# schematics.net
KiCad netlist of a schematic drawn in EasyEDA
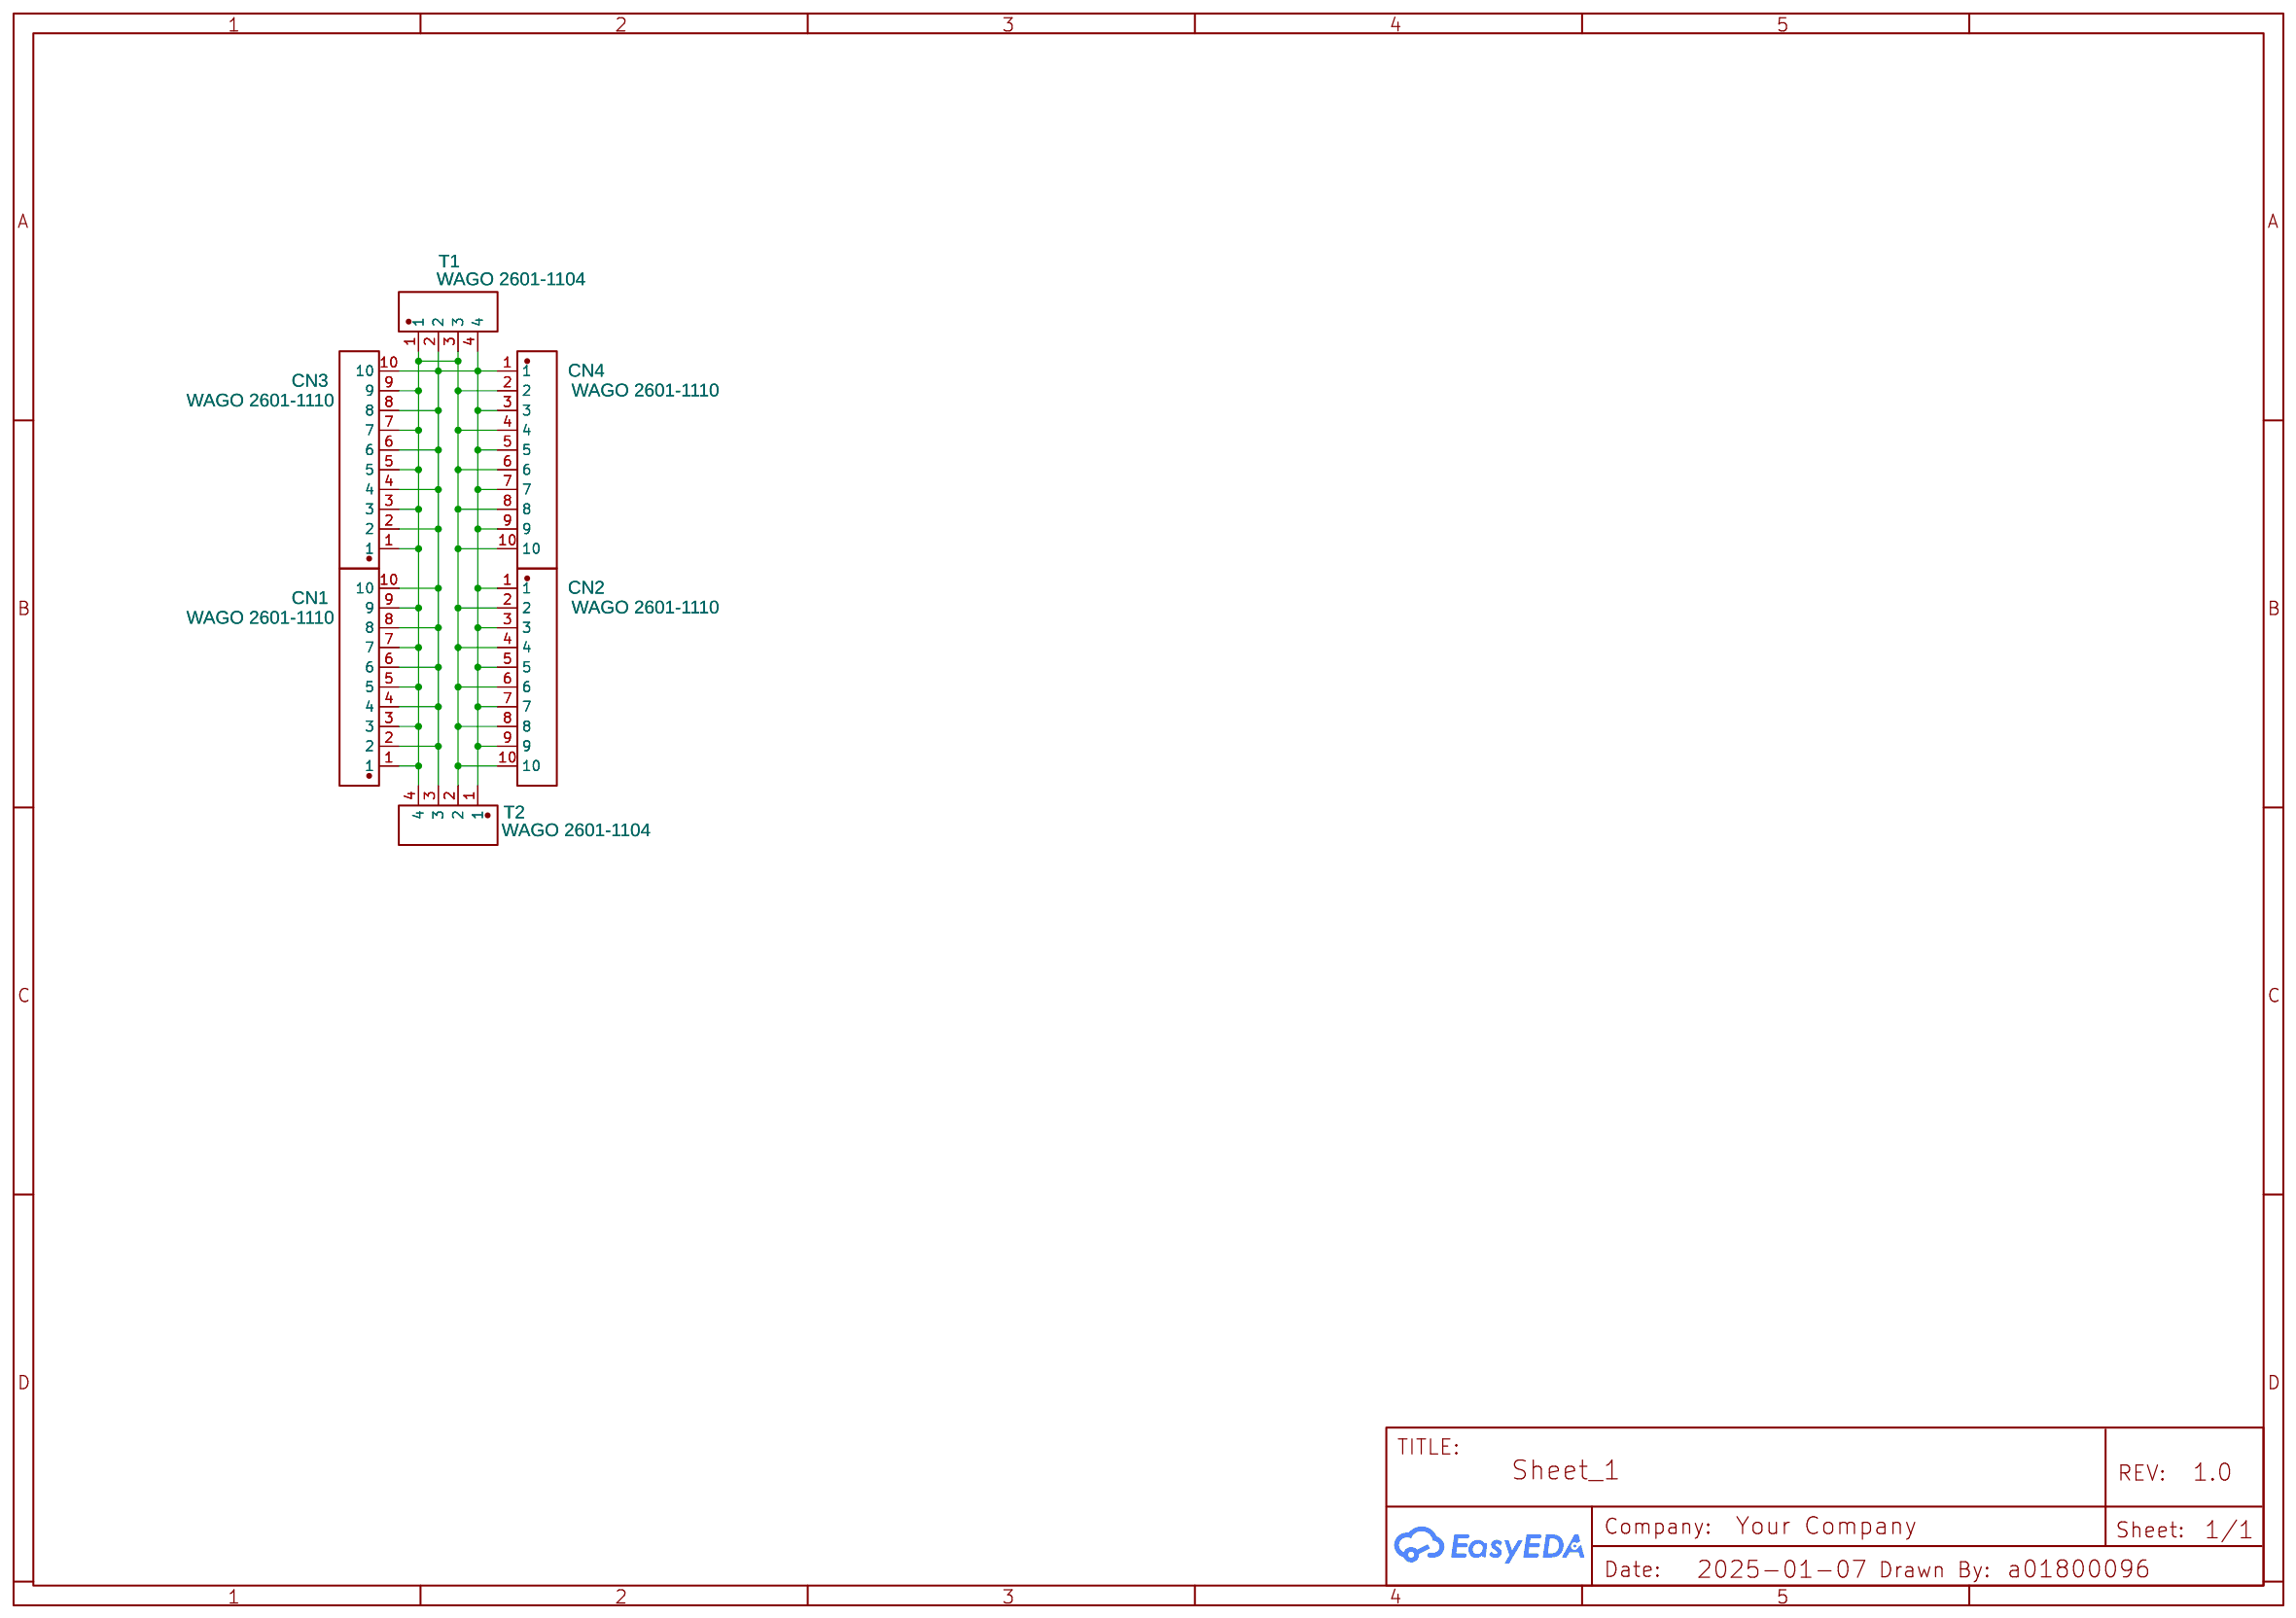
[diagram p0: PCB en Paralelo]
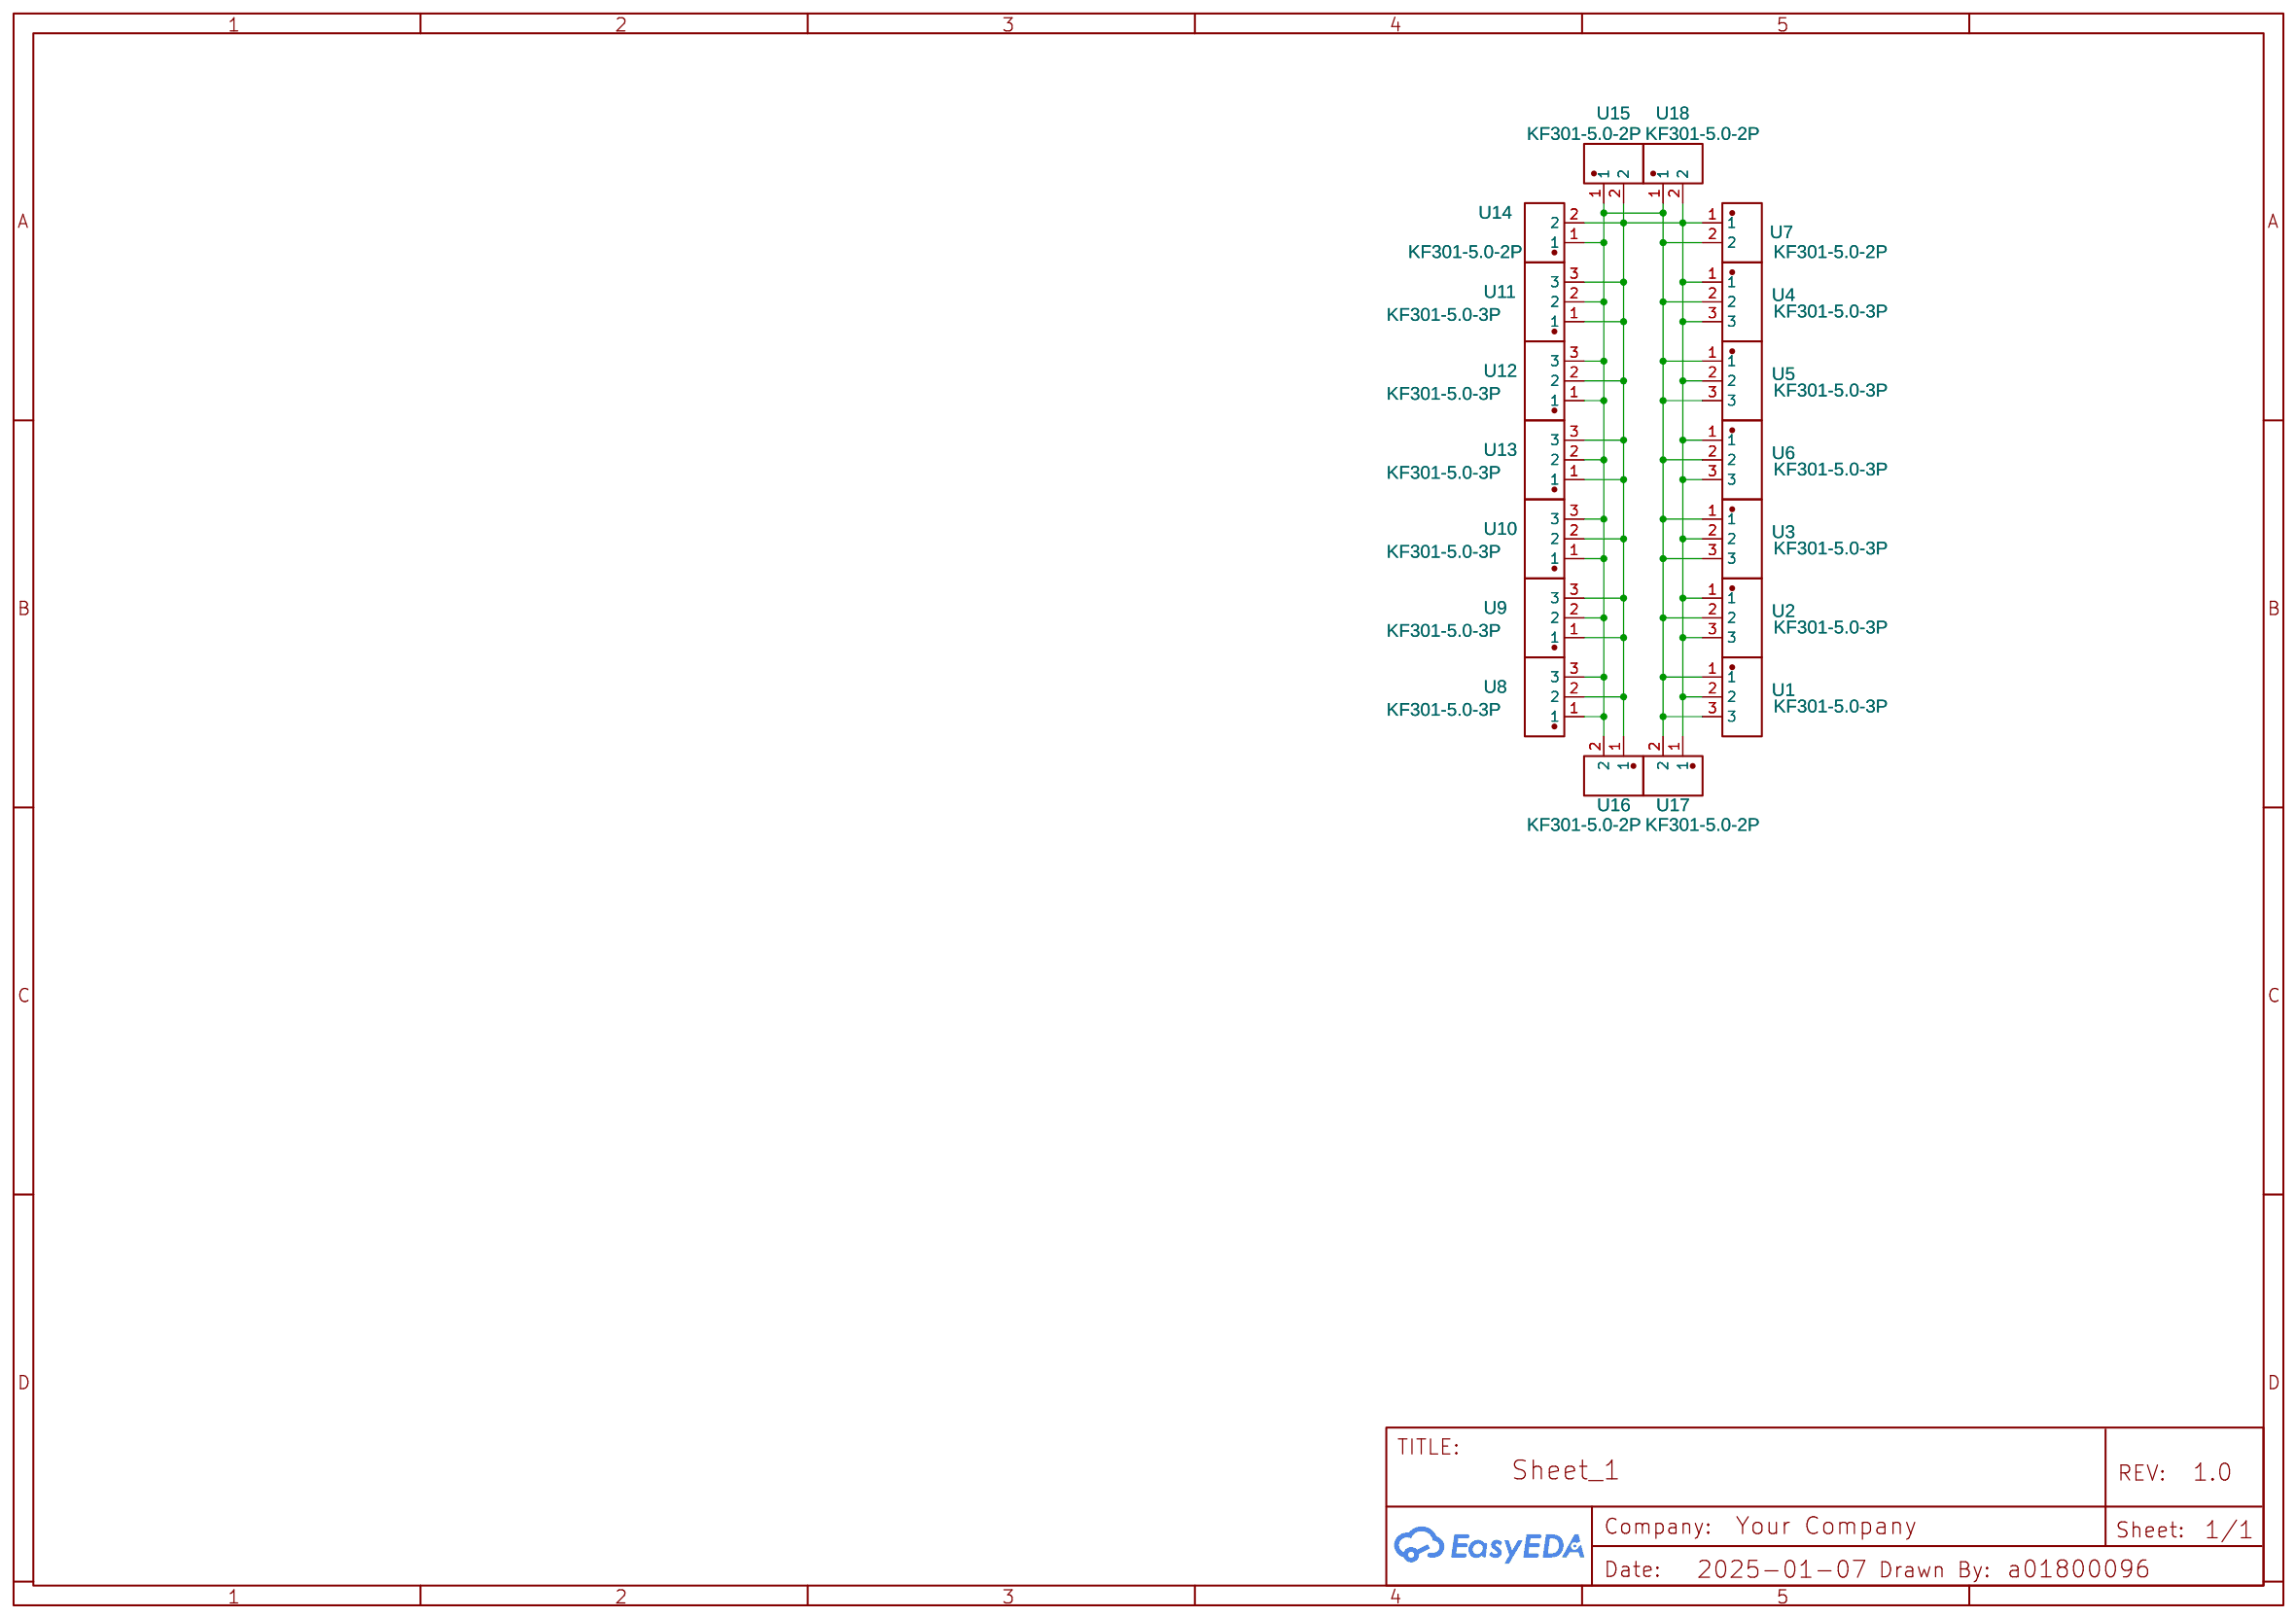
[diagram p1: PCB Final]

(export (version "E")
  (design (tool "Eeschema 10.0.6"))
  (components
    (comp (ref "CN1")
      (value "WAGO 2601-1110")
      (fields (field (name "Manufacturer Part") "CONNECTOR"))
      (libsource (lib "") (part "WAGO 2601-1110_1"))
    )
    (comp (ref "CN2")
      (value "WAGO 2601-1110")
      (fields (field (name "Manufacturer Part") "CONNECTOR"))
      (libsource (lib "") (part "WAGO 2601-1110"))
    )
    (comp (ref "CN3")
      (value "WAGO 2601-1110")
      (fields (field (name "Manufacturer Part") "CONNECTOR"))
      (libsource (lib "") (part "WAGO 2601-1110_1"))
    )
    (comp (ref "CN4")
      (value "WAGO 2601-1110")
      (fields (field (name "Manufacturer Part") "CONNECTOR"))
      (libsource (lib "") (part "WAGO 2601-1110"))
    )
    (comp (ref "T1") (value "WAGO 2601-1104") (libsource (lib "") (part "WAGO 2601-1104")))
    (comp (ref "T2") (value "WAGO 2601-1104") (libsource (lib "") (part "WAGO 2601-1104_1")))
    (comp (ref "U1")
      (value "KF301-5.0-3P")
      (fields (field (name "Manufacturer") "KEFA(科发)"))
      (libsource (lib "") (part "KF301-5.0-3P_1"))
    )
    (comp (ref "U2")
      (value "KF301-5.0-3P")
      (fields (field (name "Manufacturer") "KEFA(科发)"))
      (libsource (lib "") (part "KF301-5.0-3P_1"))
    )
    (comp (ref "U3")
      (value "KF301-5.0-3P")
      (fields (field (name "Manufacturer") "KEFA(科发)"))
      (libsource (lib "") (part "KF301-5.0-3P_1"))
    )
    (comp (ref "U4")
      (value "KF301-5.0-3P")
      (fields (field (name "Manufacturer") "KEFA(科发)"))
      (libsource (lib "") (part "KF301-5.0-3P_1"))
    )
    (comp (ref "U5")
      (value "KF301-5.0-3P")
      (fields (field (name "Manufacturer") "KEFA(科发)"))
      (libsource (lib "") (part "KF301-5.0-3P_1"))
    )
    (comp (ref "U6")
      (value "KF301-5.0-3P")
      (fields (field (name "Manufacturer") "KEFA(科发)"))
      (libsource (lib "") (part "KF301-5.0-3P_1"))
    )
    (comp (ref "U7")
      (value "KF301-5.0-2P")
      (fields (field (name "Manufacturer") "KEFA(科发)"))
      (libsource (lib "") (part "KF301-5.0-2P"))
    )
    (comp (ref "U8")
      (value "KF301-5.0-3P")
      (fields (field (name "Manufacturer") "KEFA(科发)"))
      (libsource (lib "") (part "KF301-5.0-3P"))
    )
    (comp (ref "U9")
      (value "KF301-5.0-3P")
      (fields (field (name "Manufacturer") "KEFA(科发)"))
      (libsource (lib "") (part "KF301-5.0-3P"))
    )
    (comp (ref "U10")
      (value "KF301-5.0-3P")
      (fields (field (name "Manufacturer") "KEFA(科发)"))
      (libsource (lib "") (part "KF301-5.0-3P"))
    )
    (comp (ref "U11")
      (value "KF301-5.0-3P")
      (fields (field (name "Manufacturer") "KEFA(科发)"))
      (libsource (lib "") (part "KF301-5.0-3P"))
    )
    (comp (ref "U12")
      (value "KF301-5.0-3P")
      (fields (field (name "Manufacturer") "KEFA(科发)"))
      (libsource (lib "") (part "KF301-5.0-3P"))
    )
    (comp (ref "U13")
      (value "KF301-5.0-3P")
      (fields (field (name "Manufacturer") "KEFA(科发)"))
      (libsource (lib "") (part "KF301-5.0-3P"))
    )
    (comp (ref "U14")
      (value "KF301-5.0-2P")
      (fields (field (name "Manufacturer") "KEFA(科发)"))
      (libsource (lib "") (part "KF301-5.0-2P_3"))
    )
    (comp (ref "U15")
      (value "KF301-5.0-2P")
      (fields (field (name "Manufacturer") "KEFA(科发)"))
      (libsource (lib "") (part "KF301-5.0-2P_2"))
    )
    (comp (ref "U16")
      (value "KF301-5.0-2P")
      (fields (field (name "Manufacturer") "KEFA(科发)"))
      (libsource (lib "") (part "KF301-5.0-2P_1"))
    )
    (comp (ref "U17")
      (value "KF301-5.0-2P")
      (fields (field (name "Manufacturer") "KEFA(科发)"))
      (libsource (lib "") (part "KF301-5.0-2P_1"))
    )
    (comp (ref "U18")
      (value "KF301-5.0-2P")
      (fields (field (name "Manufacturer") "KEFA(科发)"))
      (libsource (lib "") (part "KF301-5.0-2P_2"))
    )
  )
  (nets
    (net (code "1") (name "Net-(CN1-Pad1)") (class "Default")
      (node (ref "CN1") (pin "1") (pinfunction "1_1") (pintype "unspecified"))
      (node (ref "CN1") (pin "3") (pinfunction "3_3") (pintype "unspecified"))
      (node (ref "CN1") (pin "5") (pinfunction "5_5") (pintype "unspecified"))
      (node (ref "CN1") (pin "7") (pinfunction "7_7") (pintype "unspecified"))
      (node (ref "CN1") (pin "9") (pinfunction "9_9") (pintype "unspecified"))
      (node (ref "CN2") (pin "10") (pinfunction "10_10") (pintype "unspecified"))
      (node (ref "CN2") (pin "2") (pinfunction "2_2") (pintype "unspecified"))
      (node (ref "CN2") (pin "4") (pinfunction "4_4") (pintype "unspecified"))
      (node (ref "CN2") (pin "6") (pinfunction "6_6") (pintype "unspecified"))
      (node (ref "CN2") (pin "8") (pinfunction "8_8") (pintype "unspecified"))
      (node (ref "CN3") (pin "1") (pinfunction "1_1") (pintype "unspecified"))
      (node (ref "CN3") (pin "3") (pinfunction "3_3") (pintype "unspecified"))
      (node (ref "CN3") (pin "5") (pinfunction "5_5") (pintype "unspecified"))
      (node (ref "CN3") (pin "7") (pinfunction "7_7") (pintype "unspecified"))
      (node (ref "CN3") (pin "9") (pinfunction "9_9") (pintype "unspecified"))
      (node (ref "CN4") (pin "10") (pinfunction "10_10") (pintype "unspecified"))
      (node (ref "CN4") (pin "2") (pinfunction "2_2") (pintype "unspecified"))
      (node (ref "CN4") (pin "4") (pinfunction "4_4") (pintype "unspecified"))
      (node (ref "CN4") (pin "6") (pinfunction "6_6") (pintype "unspecified"))
      (node (ref "CN4") (pin "8") (pinfunction "8_8") (pintype "unspecified"))
      (node (ref "T1") (pin "1") (pinfunction "1_1") (pintype "unspecified"))
      (node (ref "T1") (pin "3") (pinfunction "3_3") (pintype "unspecified"))
      (node (ref "T2") (pin "2") (pinfunction "2_2") (pintype "unspecified"))
      (node (ref "T2") (pin "4") (pinfunction "4_4") (pintype "unspecified"))
    )
    (net (code "2") (name "Net-(CN1-Pad10)") (class "Default")
      (node (ref "CN1") (pin "10") (pinfunction "10_10") (pintype "unspecified"))
      (node (ref "CN1") (pin "2") (pinfunction "2_2") (pintype "unspecified"))
      (node (ref "CN1") (pin "4") (pinfunction "4_4") (pintype "unspecified"))
      (node (ref "CN1") (pin "6") (pinfunction "6_6") (pintype "unspecified"))
      (node (ref "CN1") (pin "8") (pinfunction "8_8") (pintype "unspecified"))
      (node (ref "CN2") (pin "1") (pinfunction "1_1") (pintype "unspecified"))
      (node (ref "CN2") (pin "3") (pinfunction "3_3") (pintype "unspecified"))
      (node (ref "CN2") (pin "5") (pinfunction "5_5") (pintype "unspecified"))
      (node (ref "CN2") (pin "7") (pinfunction "7_7") (pintype "unspecified"))
      (node (ref "CN2") (pin "9") (pinfunction "9_9") (pintype "unspecified"))
      (node (ref "CN3") (pin "10") (pinfunction "10_10") (pintype "unspecified"))
      (node (ref "CN3") (pin "2") (pinfunction "2_2") (pintype "unspecified"))
      (node (ref "CN3") (pin "4") (pinfunction "4_4") (pintype "unspecified"))
      (node (ref "CN3") (pin "6") (pinfunction "6_6") (pintype "unspecified"))
      (node (ref "CN3") (pin "8") (pinfunction "8_8") (pintype "unspecified"))
      (node (ref "CN4") (pin "1") (pinfunction "1_1") (pintype "unspecified"))
      (node (ref "CN4") (pin "3") (pinfunction "3_3") (pintype "unspecified"))
      (node (ref "CN4") (pin "5") (pinfunction "5_5") (pintype "unspecified"))
      (node (ref "CN4") (pin "7") (pinfunction "7_7") (pintype "unspecified"))
      (node (ref "CN4") (pin "9") (pinfunction "9_9") (pintype "unspecified"))
      (node (ref "T1") (pin "2") (pinfunction "2_2") (pintype "unspecified"))
      (node (ref "T1") (pin "4") (pinfunction "4_4") (pintype "unspecified"))
      (node (ref "T2") (pin "1") (pinfunction "1_1") (pintype "unspecified"))
      (node (ref "T2") (pin "3") (pinfunction "3_3") (pintype "unspecified"))
    )
    (net (code "3") (name "Net-(U1-Pad1)") (class "Default")
      (node (ref "U1") (pin "1") (pinfunction "1_1") (pintype "unspecified"))
      (node (ref "U1") (pin "3") (pinfunction "3_3") (pintype "unspecified"))
      (node (ref "U10") (pin "1") (pinfunction "1_1") (pintype "unspecified"))
      (node (ref "U10") (pin "3") (pinfunction "3_3") (pintype "unspecified"))
      (node (ref "U11") (pin "2") (pinfunction "2_2") (pintype "unspecified"))
      (node (ref "U12") (pin "1") (pinfunction "1_1") (pintype "unspecified"))
      (node (ref "U12") (pin "3") (pinfunction "3_3") (pintype "unspecified"))
      (node (ref "U13") (pin "2") (pinfunction "2_2") (pintype "unspecified"))
      (node (ref "U14") (pin "1") (pinfunction "1_1") (pintype "unspecified"))
      (node (ref "U15") (pin "1") (pinfunction "1_1") (pintype "unspecified"))
      (node (ref "U16") (pin "2") (pinfunction "2_2") (pintype "unspecified"))
      (node (ref "U17") (pin "2") (pinfunction "2_2") (pintype "unspecified"))
      (node (ref "U18") (pin "1") (pinfunction "1_1") (pintype "unspecified"))
      (node (ref "U2") (pin "2") (pinfunction "2_2") (pintype "unspecified"))
      (node (ref "U3") (pin "1") (pinfunction "1_1") (pintype "unspecified"))
      (node (ref "U3") (pin "3") (pinfunction "3_3") (pintype "unspecified"))
      (node (ref "U4") (pin "2") (pinfunction "2_2") (pintype "unspecified"))
      (node (ref "U5") (pin "1") (pinfunction "1_1") (pintype "unspecified"))
      (node (ref "U5") (pin "3") (pinfunction "3_3") (pintype "unspecified"))
      (node (ref "U6") (pin "2") (pinfunction "2_2") (pintype "unspecified"))
      (node (ref "U7") (pin "2") (pinfunction "2_2") (pintype "unspecified"))
      (node (ref "U8") (pin "1") (pinfunction "1_1") (pintype "unspecified"))
      (node (ref "U8") (pin "3") (pinfunction "3_3") (pintype "unspecified"))
      (node (ref "U9") (pin "2") (pinfunction "2_2") (pintype "unspecified"))
    )
    (net (code "4") (name "Net-(U1-Pad2)") (class "Default")
      (node (ref "U1") (pin "2") (pinfunction "2_2") (pintype "unspecified"))
      (node (ref "U10") (pin "2") (pinfunction "2_2") (pintype "unspecified"))
      (node (ref "U11") (pin "1") (pinfunction "1_1") (pintype "unspecified"))
      (node (ref "U11") (pin "3") (pinfunction "3_3") (pintype "unspecified"))
      (node (ref "U12") (pin "2") (pinfunction "2_2") (pintype "unspecified"))
      (node (ref "U13") (pin "1") (pinfunction "1_1") (pintype "unspecified"))
      (node (ref "U13") (pin "3") (pinfunction "3_3") (pintype "unspecified"))
      (node (ref "U14") (pin "2") (pinfunction "2_2") (pintype "unspecified"))
      (node (ref "U15") (pin "2") (pinfunction "2_2") (pintype "unspecified"))
      (node (ref "U16") (pin "1") (pinfunction "1_1") (pintype "unspecified"))
      (node (ref "U17") (pin "1") (pinfunction "1_1") (pintype "unspecified"))
      (node (ref "U18") (pin "2") (pinfunction "2_2") (pintype "unspecified"))
      (node (ref "U2") (pin "1") (pinfunction "1_1") (pintype "unspecified"))
      (node (ref "U2") (pin "3") (pinfunction "3_3") (pintype "unspecified"))
      (node (ref "U3") (pin "2") (pinfunction "2_2") (pintype "unspecified"))
      (node (ref "U4") (pin "1") (pinfunction "1_1") (pintype "unspecified"))
      (node (ref "U4") (pin "3") (pinfunction "3_3") (pintype "unspecified"))
      (node (ref "U5") (pin "2") (pinfunction "2_2") (pintype "unspecified"))
      (node (ref "U6") (pin "1") (pinfunction "1_1") (pintype "unspecified"))
      (node (ref "U6") (pin "3") (pinfunction "3_3") (pintype "unspecified"))
      (node (ref "U7") (pin "1") (pinfunction "1_1") (pintype "unspecified"))
      (node (ref "U8") (pin "2") (pinfunction "2_2") (pintype "unspecified"))
      (node (ref "U9") (pin "1") (pinfunction "1_1") (pintype "unspecified"))
      (node (ref "U9") (pin "3") (pinfunction "3_3") (pintype "unspecified"))
    )
  )
)
